# MIPI.net
KiCad netlist of a schematic drawn in Altium Designer
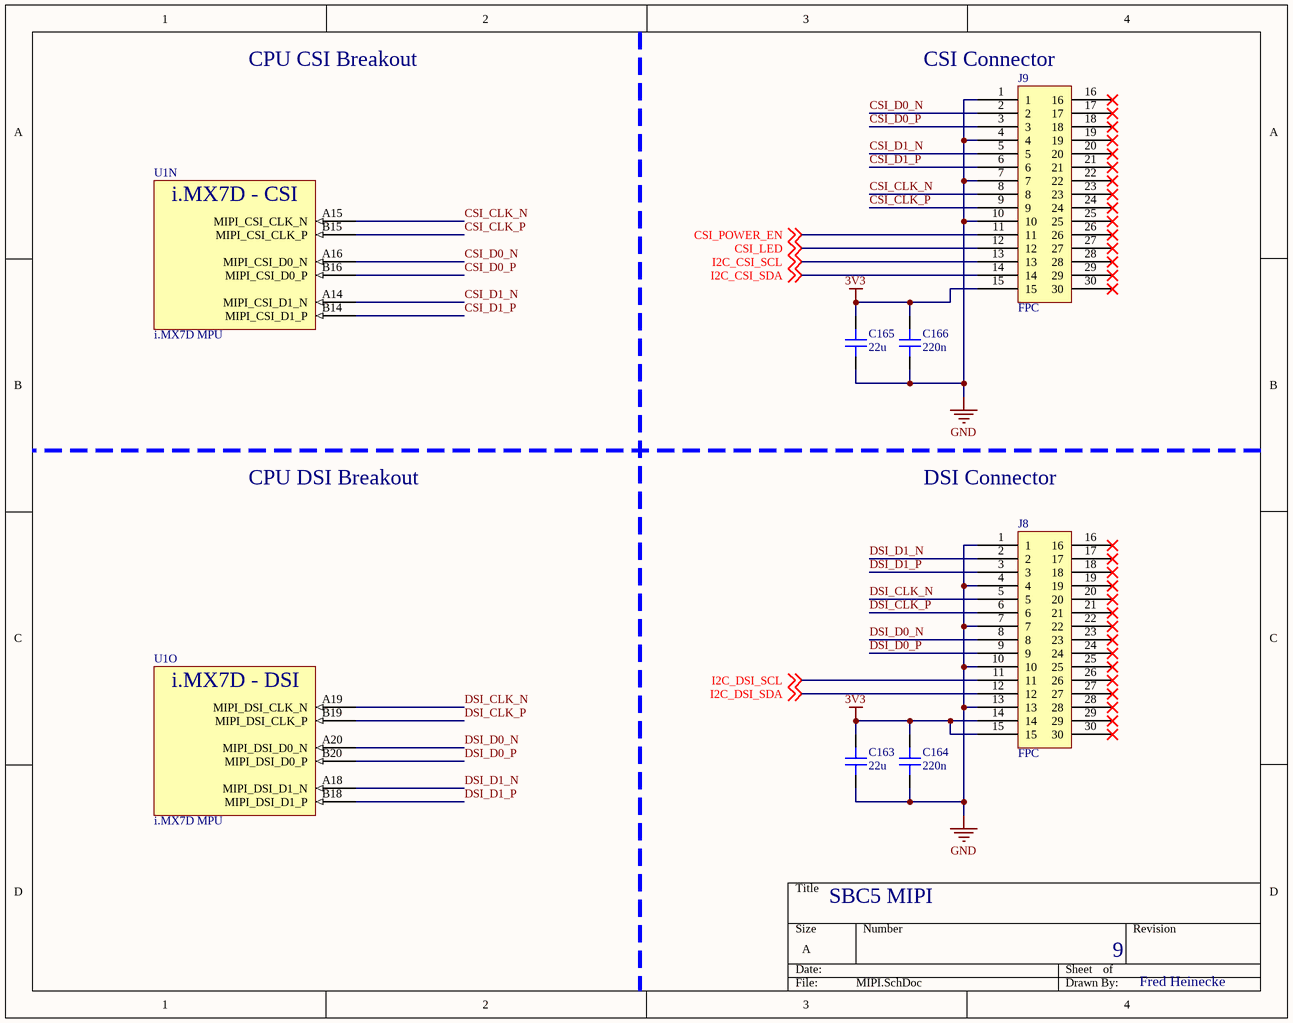
[diagram p0: MIPI.SchDoc]

(export (version "E")
  (design (tool "Eeschema 10.0.6"))
  (components
    (comp (ref "C163")
      (value "22u")
      (footprint "C0603")
      (description "0603 22 uF 10 V ±20% Tolerance X5R Multilayer Ceramic Chip Capacitor")
      (fields
        (field (name "MANUFACTURER") "Murata")
        (field (name "MANUFACTURER PART NUMBER") "GRM188R61A226ME15D")
      )
      (libsource (lib "SBC5") (part "GRM188R61A226ME15D"))
    )
    (comp (ref "C164")
      (value "220n")
      (footprint "C0201")
      (description "Cap Ceramic Monolithic 0.22uF 16VDC 10% SMD Paper T/R")
      (fields
        (field (name "MANUFACTURER") "Murata")
        (field (name "MANUFACTURER PART NUMBER") "GRM033R61C224KE14D")
      )
      (libsource (lib "SBC5") (part "GRM033R61C224KE14D"))
    )
    (comp (ref "C165")
      (value "22u")
      (footprint "C0603")
      (description "0603 22 uF 10 V ±20% Tolerance X5R Multilayer Ceramic Chip Capacitor")
      (fields
        (field (name "MANUFACTURER") "Murata")
        (field (name "MANUFACTURER PART NUMBER") "GRM188R61A226ME15D")
      )
      (libsource (lib "SBC5") (part "GRM188R61A226ME15D"))
    )
    (comp (ref "C166")
      (value "220n")
      (footprint "C0201")
      (description "Cap Ceramic Monolithic 0.22uF 16VDC 10% SMD Paper T/R")
      (fields
        (field (name "MANUFACTURER") "Murata")
        (field (name "MANUFACTURER PART NUMBER") "GRM033R61C224KE14D")
      )
      (libsource (lib "SBC5") (part "GRM033R61C224KE14D"))
    )
    (comp (ref "J8")
      (value "FPC")
      (footprint "1-1734248-5")
      (description "FFC & FPC Connectors 15P 1.0 FPC, Zip V/T SMT")
      (fields
        (field (name "MANUFACTURER") "TE Connectivity")
        (field (name "MANUFACTURER PART NUMBER") "1-1734248-5")
      )
      (libsource (lib "SBC5") (part "1-1734248-5"))
    )
    (comp (ref "J9")
      (value "FPC")
      (footprint "1-1734248-5")
      (description "FFC & FPC Connectors 15P 1.0 FPC, Zip V/T SMT")
      (fields
        (field (name "MANUFACTURER") "TE Connectivity")
        (field (name "MANUFACTURER PART NUMBER") "1-1734248-5")
      )
      (libsource (lib "SBC5") (part "1-1734248-5"))
    )
    (comp (ref "U1")
      (value "i.MX7D MPU")
      (footprint "BGA541C75P25X25_1900X1900X140")
      (description "Heterogeneous Multicore Processing Architecture")
      (fields
        (field (name "MANUFACTURER") "NXP Freescale")
        (field (name "MANUFACTURER PART NUMBER") "MCIMX7D2DVM12SD")
      )
      (libsource (lib "SBC5") (part "MCIMX7D2DVM12SD"))
    )
  )
  (nets
    (net (code "1") (name "/CSI_CLK_N") (class "Default")
      (node (ref "J9") (pin "8") (pinfunction "8_8") (pintype "passive"))
      (node (ref "U1") (pin "A15") (pinfunction "MIPI_CSI_CLK_N_A15") (pintype "input"))
    )
    (net (code "2") (name "/CSI_CLK_P") (class "Default")
      (node (ref "J9") (pin "9") (pinfunction "9_9") (pintype "passive"))
      (node (ref "U1") (pin "B15") (pinfunction "MIPI_CSI_CLK_P_B15") (pintype "input"))
    )
    (net (code "3") (name "/CSI_D0_N") (class "Default")
      (node (ref "J9") (pin "2") (pinfunction "2_2") (pintype "passive"))
      (node (ref "U1") (pin "A16") (pinfunction "MIPI_CSI_D0_N_A16") (pintype "input"))
    )
    (net (code "4") (name "/CSI_D0_P") (class "Default")
      (node (ref "J9") (pin "3") (pinfunction "3_3") (pintype "passive"))
      (node (ref "U1") (pin "B16") (pinfunction "MIPI_CSI_D0_P_B16") (pintype "input"))
    )
    (net (code "5") (name "/CSI_D1_N") (class "Default")
      (node (ref "J9") (pin "5") (pinfunction "5_5") (pintype "passive"))
      (node (ref "U1") (pin "A14") (pinfunction "MIPI_CSI_D1_N_A14") (pintype "input"))
    )
    (net (code "6") (name "/CSI_D1_P") (class "Default")
      (node (ref "J9") (pin "6") (pinfunction "6_6") (pintype "passive"))
      (node (ref "U1") (pin "B14") (pinfunction "MIPI_CSI_D1_P_B14") (pintype "input"))
    )
    (net (code "7") (name "/DSI_CLK_N") (class "Default")
      (node (ref "J8") (pin "5") (pinfunction "5_5") (pintype "passive"))
      (node (ref "U1") (pin "A19") (pinfunction "MIPI_DSI_CLK_N_A19") (pintype "input"))
    )
    (net (code "8") (name "/DSI_CLK_P") (class "Default")
      (node (ref "J8") (pin "6") (pinfunction "6_6") (pintype "passive"))
      (node (ref "U1") (pin "B19") (pinfunction "MIPI_DSI_CLK_P_B19") (pintype "input"))
    )
    (net (code "9") (name "/DSI_D0_N") (class "Default")
      (node (ref "J8") (pin "8") (pinfunction "8_8") (pintype "passive"))
      (node (ref "U1") (pin "A20") (pinfunction "MIPI_DSI_D0_N_A20") (pintype "input"))
    )
    (net (code "10") (name "/DSI_D0_P") (class "Default")
      (node (ref "J8") (pin "9") (pinfunction "9_9") (pintype "passive"))
      (node (ref "U1") (pin "B20") (pinfunction "MIPI_DSI_D0_P_B20") (pintype "input"))
    )
    (net (code "11") (name "/DSI_D1_N") (class "Default")
      (node (ref "J8") (pin "2") (pinfunction "2_2") (pintype "passive"))
      (node (ref "U1") (pin "A18") (pinfunction "MIPI_DSI_D1_N_A18") (pintype "input"))
    )
    (net (code "12") (name "/DSI_D1_P") (class "Default")
      (node (ref "J8") (pin "3") (pinfunction "3_3") (pintype "passive"))
      (node (ref "U1") (pin "B18") (pinfunction "MIPI_DSI_D1_P_B18") (pintype "input"))
    )
    (net (code "13") (name "3V3") (class "Default")
      (node (ref "C163") (pin "2") (pinfunction "2_2") (pintype "passive"))
      (node (ref "C164") (pin "2") (pinfunction "2_2") (pintype "passive"))
      (node (ref "C165") (pin "2") (pinfunction "2_2") (pintype "passive"))
      (node (ref "C166") (pin "2") (pinfunction "2_2") (pintype "passive"))
      (node (ref "J8") (pin "14") (pinfunction "14_14") (pintype "passive"))
      (node (ref "J8") (pin "15") (pinfunction "15_15") (pintype "passive"))
      (node (ref "J9") (pin "15") (pinfunction "15_15") (pintype "passive"))
    )
    (net (code "14") (name "CSI_LED") (class "Default")
      (node (ref "J9") (pin "12") (pinfunction "12_12") (pintype "passive"))
    )
    (net (code "15") (name "CSI_POWER_EN") (class "Default")
      (node (ref "J9") (pin "11") (pinfunction "11_11") (pintype "passive"))
    )
    (net (code "16") (name "GND") (class "Default")
      (node (ref "C163") (pin "1") (pinfunction "1_1") (pintype "passive"))
      (node (ref "C164") (pin "1") (pinfunction "1_1") (pintype "passive"))
      (node (ref "C165") (pin "1") (pinfunction "1_1") (pintype "passive"))
      (node (ref "C166") (pin "1") (pinfunction "1_1") (pintype "passive"))
      (node (ref "J8") (pin "1") (pinfunction "1_1") (pintype "passive"))
      (node (ref "J8") (pin "10") (pinfunction "10_10") (pintype "passive"))
      (node (ref "J8") (pin "13") (pinfunction "13_13") (pintype "passive"))
      (node (ref "J8") (pin "4") (pinfunction "4_4") (pintype "passive"))
      (node (ref "J8") (pin "7") (pinfunction "7_7") (pintype "passive"))
      (node (ref "J9") (pin "1") (pinfunction "1_1") (pintype "passive"))
      (node (ref "J9") (pin "10") (pinfunction "10_10") (pintype "passive"))
      (node (ref "J9") (pin "4") (pinfunction "4_4") (pintype "passive"))
      (node (ref "J9") (pin "7") (pinfunction "7_7") (pintype "passive"))
    )
    (net (code "17") (name "I2C_CSI_SCL") (class "Default")
      (node (ref "J9") (pin "13") (pinfunction "13_13") (pintype "passive"))
    )
    (net (code "18") (name "I2C_CSI_SDA") (class "Default")
      (node (ref "J9") (pin "14") (pinfunction "14_14") (pintype "passive"))
    )
    (net (code "19") (name "I2C_DSI_SCL") (class "Default")
      (node (ref "J8") (pin "11") (pinfunction "11_11") (pintype "passive"))
    )
    (net (code "20") (name "I2C_DSI_SDA") (class "Default")
      (node (ref "J8") (pin "12") (pinfunction "12_12") (pintype "passive"))
    )
    (net (code "21") (name "unconnected-(J8-Pad16)") (class "Default")
      (node (ref "J8") (pin "16") (pinfunction "16_16") (pintype "passive+no_connect"))
    )
    (net (code "22") (name "unconnected-(J8-Pad17)") (class "Default")
      (node (ref "J8") (pin "17") (pinfunction "17_17") (pintype "passive+no_connect"))
    )
    (net (code "23") (name "unconnected-(J8-Pad18)") (class "Default")
      (node (ref "J8") (pin "18") (pinfunction "18_18") (pintype "passive+no_connect"))
    )
    (net (code "24") (name "unconnected-(J8-Pad19)") (class "Default")
      (node (ref "J8") (pin "19") (pinfunction "19_19") (pintype "passive+no_connect"))
    )
    (net (code "25") (name "unconnected-(J8-Pad20)") (class "Default")
      (node (ref "J8") (pin "20") (pinfunction "20_20") (pintype "passive+no_connect"))
    )
    (net (code "26") (name "unconnected-(J8-Pad21)") (class "Default")
      (node (ref "J8") (pin "21") (pinfunction "21_21") (pintype "passive+no_connect"))
    )
    (net (code "27") (name "unconnected-(J8-Pad22)") (class "Default")
      (node (ref "J8") (pin "22") (pinfunction "22_22") (pintype "passive+no_connect"))
    )
    (net (code "28") (name "unconnected-(J8-Pad23)") (class "Default")
      (node (ref "J8") (pin "23") (pinfunction "23_23") (pintype "passive+no_connect"))
    )
    (net (code "29") (name "unconnected-(J8-Pad24)") (class "Default")
      (node (ref "J8") (pin "24") (pinfunction "24_24") (pintype "passive+no_connect"))
    )
    (net (code "30") (name "unconnected-(J8-Pad25)") (class "Default")
      (node (ref "J8") (pin "25") (pinfunction "25_25") (pintype "passive+no_connect"))
    )
    (net (code "31") (name "unconnected-(J8-Pad26)") (class "Default")
      (node (ref "J8") (pin "26") (pinfunction "26_26") (pintype "passive+no_connect"))
    )
    (net (code "32") (name "unconnected-(J8-Pad27)") (class "Default")
      (node (ref "J8") (pin "27") (pinfunction "27_27") (pintype "passive+no_connect"))
    )
    (net (code "33") (name "unconnected-(J8-Pad28)") (class "Default")
      (node (ref "J8") (pin "28") (pinfunction "28_28") (pintype "passive+no_connect"))
    )
    (net (code "34") (name "unconnected-(J8-Pad29)") (class "Default")
      (node (ref "J8") (pin "29") (pinfunction "29_29") (pintype "passive+no_connect"))
    )
    (net (code "35") (name "unconnected-(J8-Pad30)") (class "Default")
      (node (ref "J8") (pin "30") (pinfunction "30_30") (pintype "passive+no_connect"))
    )
    (net (code "36") (name "unconnected-(J9-Pad16)") (class "Default")
      (node (ref "J9") (pin "16") (pinfunction "16_16") (pintype "passive+no_connect"))
    )
    (net (code "37") (name "unconnected-(J9-Pad17)") (class "Default")
      (node (ref "J9") (pin "17") (pinfunction "17_17") (pintype "passive+no_connect"))
    )
    (net (code "38") (name "unconnected-(J9-Pad18)") (class "Default")
      (node (ref "J9") (pin "18") (pinfunction "18_18") (pintype "passive+no_connect"))
    )
    (net (code "39") (name "unconnected-(J9-Pad19)") (class "Default")
      (node (ref "J9") (pin "19") (pinfunction "19_19") (pintype "passive+no_connect"))
    )
    (net (code "40") (name "unconnected-(J9-Pad20)") (class "Default")
      (node (ref "J9") (pin "20") (pinfunction "20_20") (pintype "passive+no_connect"))
    )
    (net (code "41") (name "unconnected-(J9-Pad21)") (class "Default")
      (node (ref "J9") (pin "21") (pinfunction "21_21") (pintype "passive+no_connect"))
    )
    (net (code "42") (name "unconnected-(J9-Pad22)") (class "Default")
      (node (ref "J9") (pin "22") (pinfunction "22_22") (pintype "passive+no_connect"))
    )
    (net (code "43") (name "unconnected-(J9-Pad23)") (class "Default")
      (node (ref "J9") (pin "23") (pinfunction "23_23") (pintype "passive+no_connect"))
    )
    (net (code "44") (name "unconnected-(J9-Pad24)") (class "Default")
      (node (ref "J9") (pin "24") (pinfunction "24_24") (pintype "passive+no_connect"))
    )
    (net (code "45") (name "unconnected-(J9-Pad25)") (class "Default")
      (node (ref "J9") (pin "25") (pinfunction "25_25") (pintype "passive+no_connect"))
    )
    (net (code "46") (name "unconnected-(J9-Pad26)") (class "Default")
      (node (ref "J9") (pin "26") (pinfunction "26_26") (pintype "passive+no_connect"))
    )
    (net (code "47") (name "unconnected-(J9-Pad27)") (class "Default")
      (node (ref "J9") (pin "27") (pinfunction "27_27") (pintype "passive+no_connect"))
    )
    (net (code "48") (name "unconnected-(J9-Pad28)") (class "Default")
      (node (ref "J9") (pin "28") (pinfunction "28_28") (pintype "passive+no_connect"))
    )
    (net (code "49") (name "unconnected-(J9-Pad29)") (class "Default")
      (node (ref "J9") (pin "29") (pinfunction "29_29") (pintype "passive+no_connect"))
    )
    (net (code "50") (name "unconnected-(J9-Pad30)") (class "Default")
      (node (ref "J9") (pin "30") (pinfunction "30_30") (pintype "passive+no_connect"))
    )
  )
)
